# 0001.net
KiCad netlist of a schematic drawn in EasyEDA
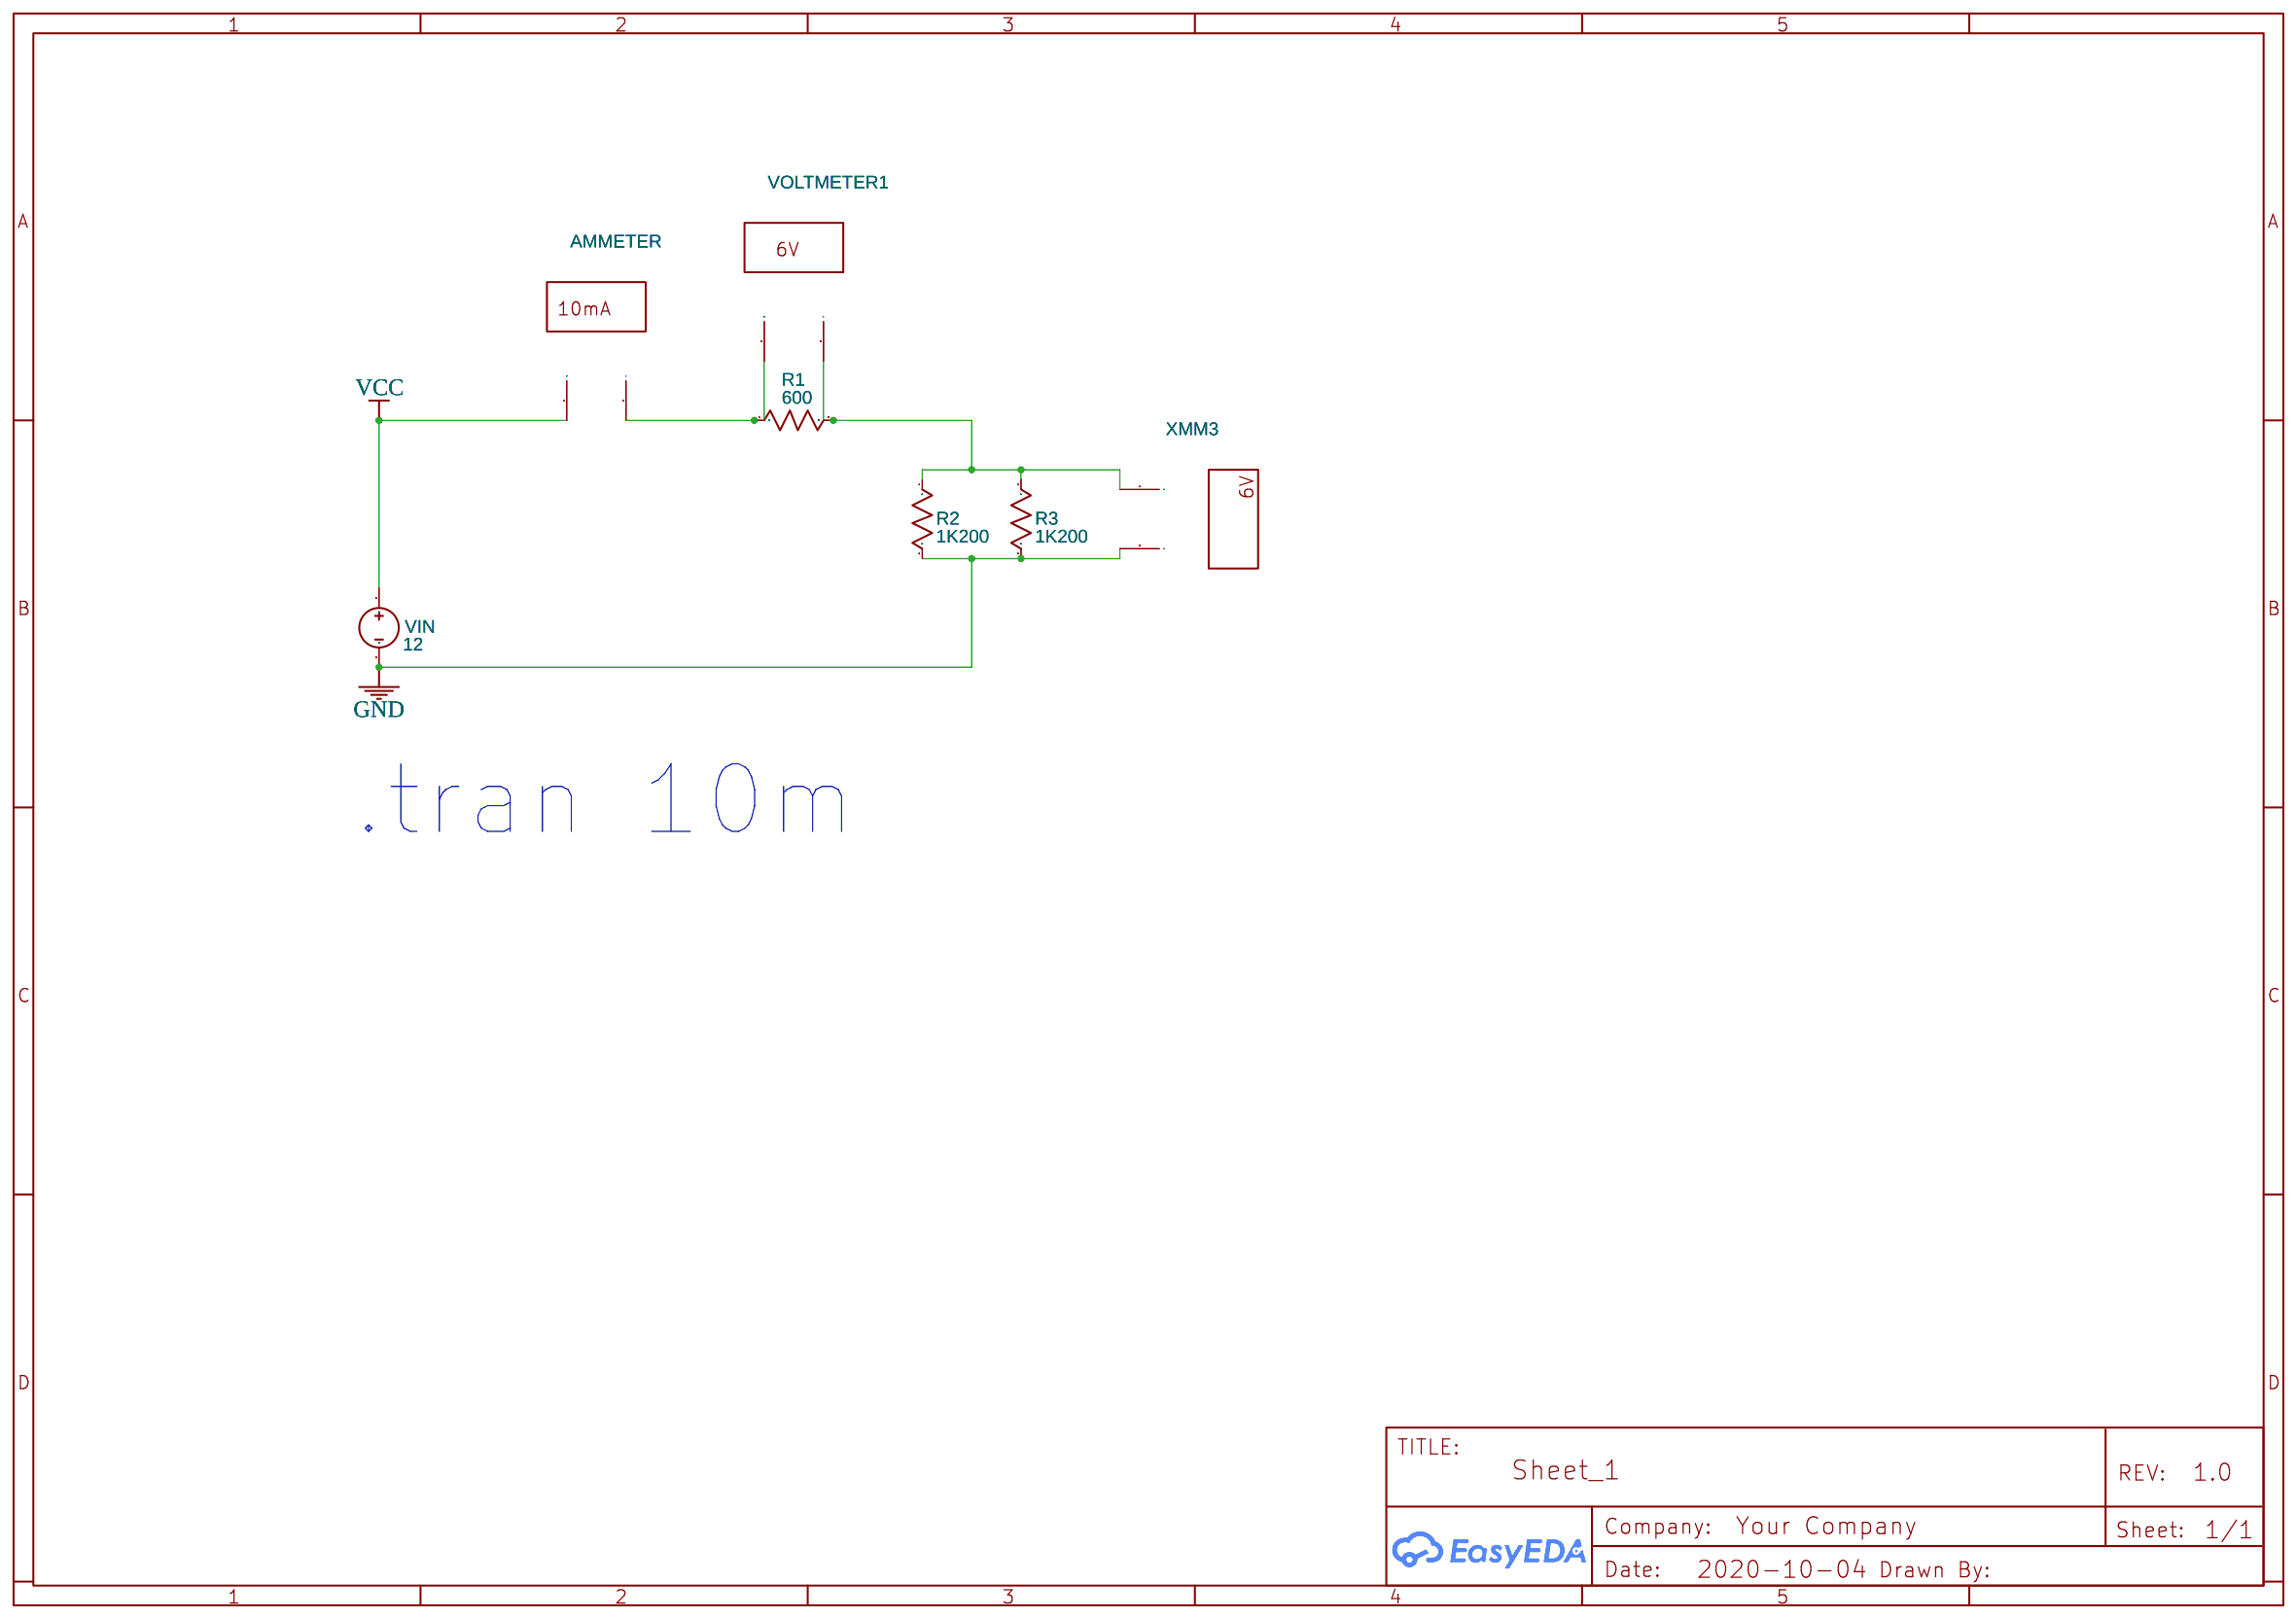
[diagram p0: schematic sheet]

(export (version "E")
  (design (tool "Eeschema 10.0.6"))
  (components
    (comp (ref "AMMETER") (value "Multimeter") (libsource (lib "") (part "MULTIMETER_1")))
    (comp (ref "R1") (value "600") (libsource (lib "") (part "Resistor_US_1")))
    (comp (ref "R2") (value "1K200") (libsource (lib "") (part "Resistor_US")))
    (comp (ref "R3") (value "1K200") (libsource (lib "") (part "Resistor_US")))
    (comp (ref "VIN") (value "12") (libsource (lib "") (part "VDC")))
    (comp (ref "VOLTMETER1") (value "Multimeter") (libsource (lib "") (part "MULTIMETER")))
    (comp (ref "XMM3") (value "Multimeter") (libsource (lib "") (part "MULTIMETER_2")))
  )
  (nets
    (net (code "1") (name "GND") (class "Default")
      (node (ref "R2") (pin "2") (pinfunction "2_2") (pintype "unspecified"))
      (node (ref "R3") (pin "2") (pinfunction "2_2") (pintype "unspecified"))
      (node (ref "VIN") (pin "2") (pinfunction "2_2") (pintype "unspecified"))
      (node (ref "XMM3") (pin "2") (pinfunction "I_2") (pintype "unspecified"))
    )
    (net (code "2") (name "Net-(AMMETER-I)") (class "Default")
      (node (ref "AMMETER") (pin "2") (pinfunction "I_2") (pintype "unspecified"))
      (node (ref "R1") (pin "1") (pinfunction "1_1") (pintype "unspecified"))
      (node (ref "VOLTMETER1") (pin "1") (pinfunction "+_1") (pintype "unspecified"))
    )
    (net (code "3") (name "Net-(VOLTMETER1-I)") (class "Default")
      (node (ref "R1") (pin "2") (pinfunction "2_2") (pintype "unspecified"))
      (node (ref "R2") (pin "1") (pinfunction "1_1") (pintype "unspecified"))
      (node (ref "R3") (pin "1") (pinfunction "1_1") (pintype "unspecified"))
      (node (ref "VOLTMETER1") (pin "2") (pinfunction "I_2") (pintype "unspecified"))
      (node (ref "XMM3") (pin "1") (pinfunction "+_1") (pintype "unspecified"))
    )
    (net (code "4") (name "VCC") (class "Default")
      (node (ref "AMMETER") (pin "1") (pinfunction "+_1") (pintype "unspecified"))
      (node (ref "VIN") (pin "1") (pinfunction "1_1") (pintype "unspecified"))
    )
  )
)
